# RAK3112_RS485_P2P_Node_V1_1.net
KiCad netlist of a schematic drawn in EasyEDA Pro
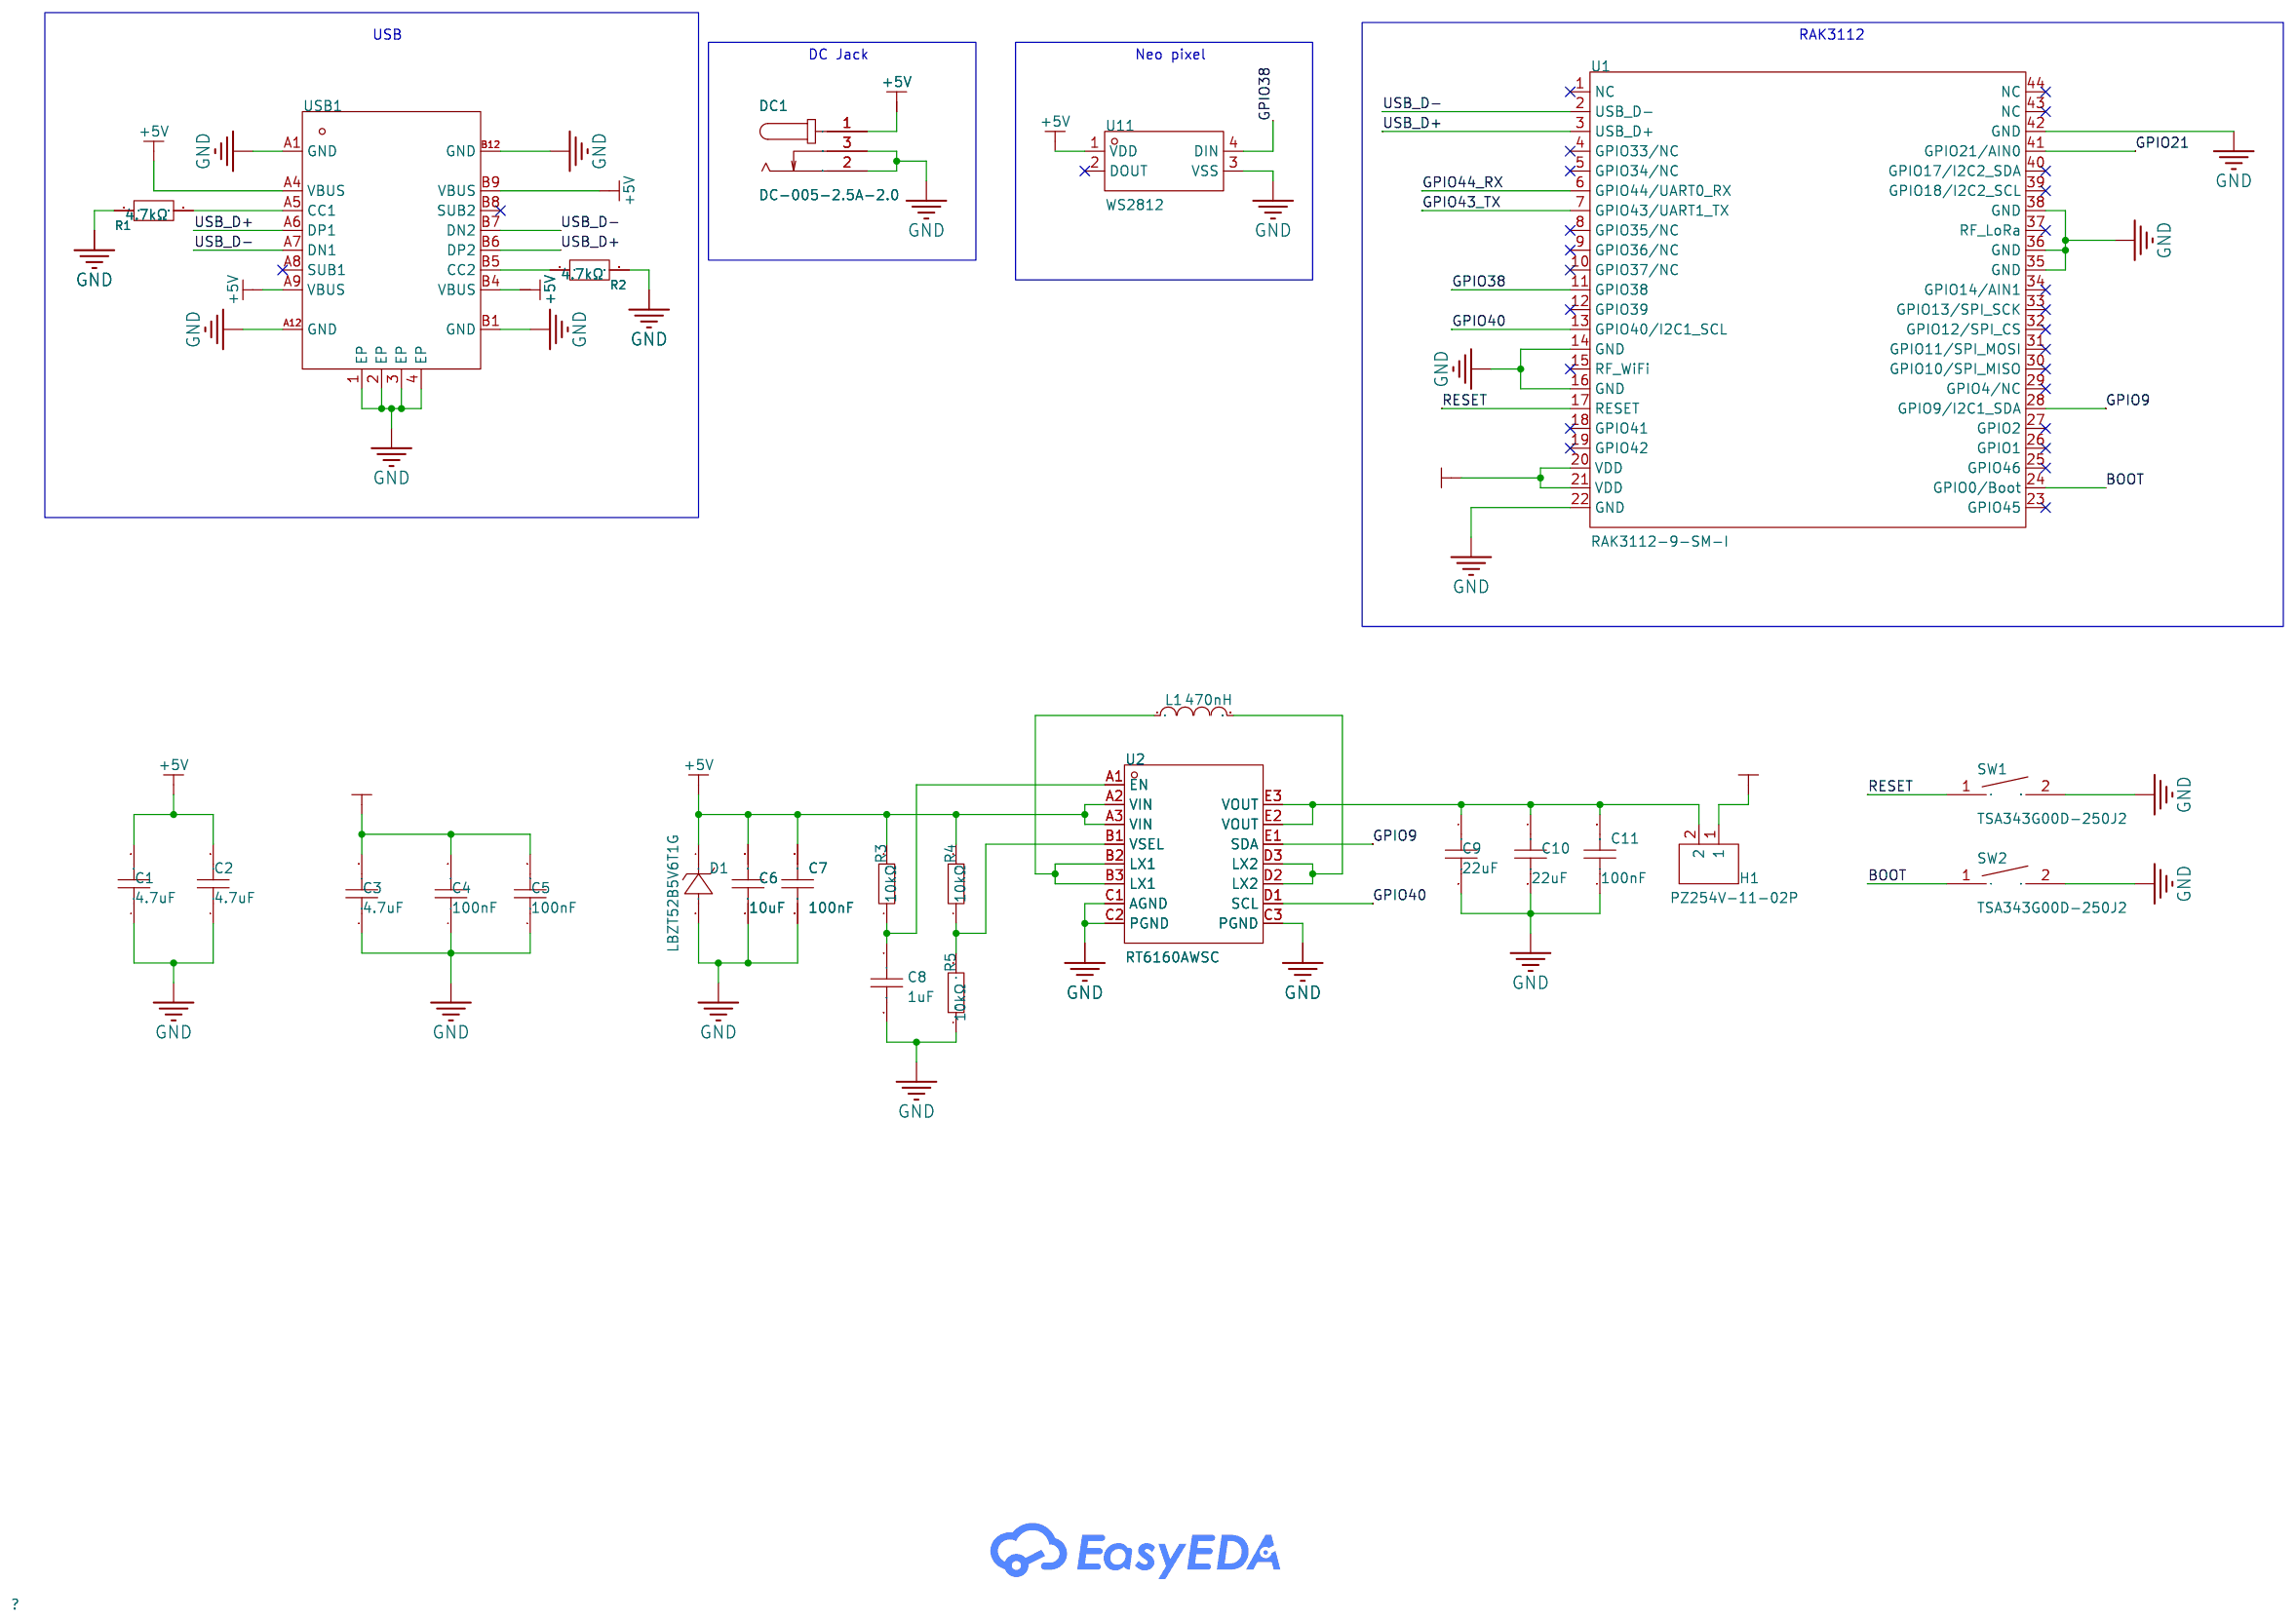
[diagram p0: P1]
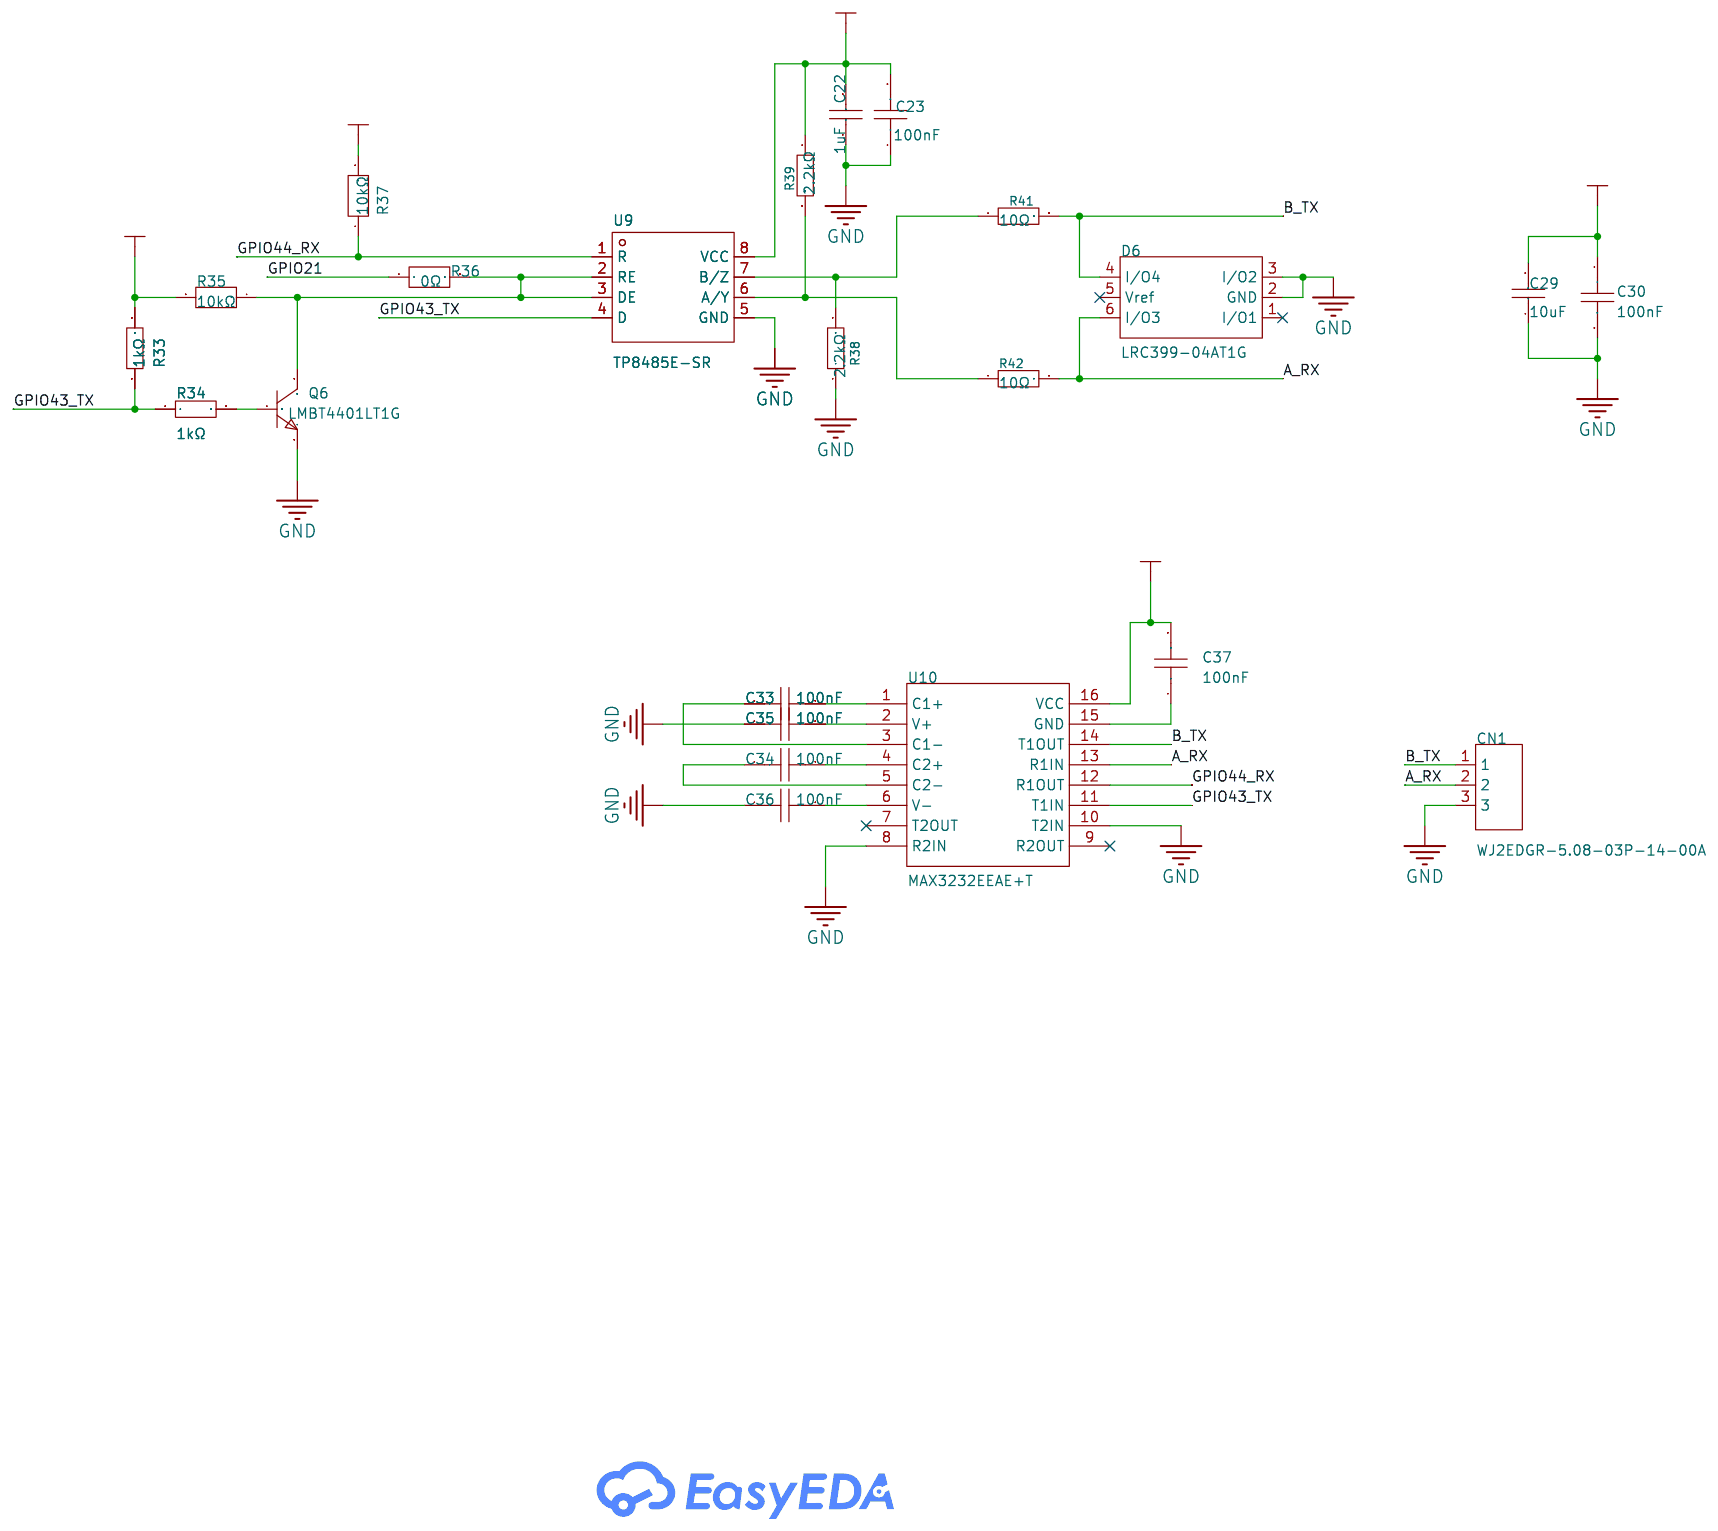
[diagram p1: RS484]

(export (version "E")
  (design (tool "Eeschema 10.0.6"))
  (components
    (comp (ref "C1")
      (value "4.7uF")
      (footprint "easyedapro:C0603")
      (description "Capacitance:4.7uF Tolerance:±10% Tolerance:±10% Voltage Rating:16V Temperature Coefficient:X5R")
      (fields
        (field (name "Manufacturer Part") "CL10A475KO8NNNC")
        (field (name "Manufacturer") "SAMSUNG(三星)")
      )
      (libsource (lib "easyedapro") (part "CL10A475KO8NNNC"))
    )
    (comp (ref "C2")
      (value "4.7uF")
      (footprint "easyedapro:C0603")
      (description "Capacitance:4.7uF Tolerance:±10% Tolerance:±10% Voltage Rating:16V Temperature Coefficient:X5R")
      (fields
        (field (name "Manufacturer Part") "CL10A475KO8NNNC")
        (field (name "Manufacturer") "SAMSUNG(三星)")
      )
      (libsource (lib "easyedapro") (part "CL10A475KO8NNNC"))
    )
    (comp (ref "C3")
      (value "4.7uF")
      (footprint "easyedapro:C0603")
      (description "Capacitance:4.7uF Tolerance:±10% Tolerance:±10% Voltage Rating:16V Temperature Coefficient:X5R")
      (fields
        (field (name "Manufacturer Part") "CL10A475KO8NNNC")
        (field (name "Manufacturer") "SAMSUNG(三星)")
      )
      (libsource (lib "easyedapro") (part "CL10A475KO8NNNC"))
    )
    (comp (ref "C4")
      (value "100nF")
      (footprint "easyedapro:C0603")
      (description "Capacitance:100nF Tolerance:±10% Tolerance:±10% Voltage Rating:50V Temperature Coefficient:X7R")
      (fields
        (field (name "Manufacturer Part") "TCC0603X7R104K500CT")
        (field (name "Manufacturer") "CCTC(三环)")
      )
      (libsource (lib "easyedapro") (part "TCC0603X7R104K500CT"))
    )
    (comp (ref "C5")
      (value "100nF")
      (footprint "easyedapro:C0603")
      (description "Capacitance:100nF Tolerance:±10% Tolerance:±10% Voltage Rating:50V Temperature Coefficient:X7R")
      (fields
        (field (name "Manufacturer Part") "TCC0603X7R104K500CT")
        (field (name "Manufacturer") "CCTC(三环)")
      )
      (libsource (lib "easyedapro") (part "TCC0603X7R104K500CT"))
    )
    (comp (ref "C6")
      (value "10uF")
      (footprint "easyedapro:C0603")
      (description "Capacitance:10uF Tolerance:±10% Tolerance:±10% Voltage Rating:10V Temperature Coefficient:X5R")
      (fields
        (field (name "Manufacturer Part") "CGA0603X5R106K100JT")
        (field (name "Manufacturer") "HRE(芯声)")
      )
      (libsource (lib "easyedapro") (part "CGA0603X5R106K100JT"))
    )
    (comp (ref "C7")
      (value "100nF")
      (footprint "easyedapro:C0603")
      (description "Capacitance:100nF Tolerance:±10% Tolerance:±10% Voltage Rating:50V Temperature Coefficient:X7R")
      (fields
        (field (name "Manufacturer Part") "TCC0603X7R104K500CT")
        (field (name "Manufacturer") "CCTC(三环)")
      )
      (libsource (lib "easyedapro") (part "TCC0603X7R104K500CT"))
    )
    (comp (ref "C8")
      (value "1uF")
      (footprint "easyedapro:C0603")
      (description "Capacitance:1uF Tolerance:±10% Tolerance:±10% Voltage Rating:50V Temperature Coefficient:X7R")
      (fields
        (field (name "Manufacturer Part") "CL10B105KB8NQNC")
        (field (name "Manufacturer") "SAMSUNG(三星)")
      )
      (libsource (lib "easyedapro") (part "CL10B105KB8NQNC"))
    )
    (comp (ref "C9")
      (value "22uF")
      (footprint "easyedapro:C0603")
      (description "Capacitance:22uF Tolerance:±20% Tolerance:±20% Voltage Rating:6.3V Temperature Coefficient:X5R")
      (fields
        (field (name "Manufacturer Part") "CL10A226MQ8NRNC")
        (field (name "Manufacturer") "SAMSUNG(三星)")
      )
      (libsource (lib "easyedapro") (part "CL10A226MQ8NRNC"))
    )
    (comp (ref "C10")
      (value "22uF")
      (footprint "easyedapro:C0603")
      (description "Capacitance:22uF Tolerance:±20% Tolerance:±20% Voltage Rating:6.3V Temperature Coefficient:X5R")
      (fields
        (field (name "Manufacturer Part") "CL10A226MQ8NRNC")
        (field (name "Manufacturer") "SAMSUNG(三星)")
      )
      (libsource (lib "easyedapro") (part "CL10A226MQ8NRNC"))
    )
    (comp (ref "C11")
      (value "100nF")
      (footprint "easyedapro:C0603")
      (description "Capacitance:100nF Tolerance:±10% Tolerance:±10% Voltage Rating:50V Temperature Coefficient:X7R")
      (fields
        (field (name "Manufacturer Part") "TCC0603X7R104K500CT")
        (field (name "Manufacturer") "CCTC(三环)")
      )
      (libsource (lib "easyedapro") (part "TCC0603X7R104K500CT"))
    )
    (comp (ref "D1")
      (value "LBZT52B5V6T1G")
      (footprint "easyedapro:SOD-123_L2.7-W1.6-LS3.7-RD-1")
      (fields (field (name "Manufacturer") "LRC(乐山无线电)"))
      (libsource (lib "easyedapro") (part "LBZT52B5V6T1G"))
    )
    (comp (ref "DC1")
      (value "DC-005-2.5A-2.0")
      (footprint "easyedapro:CONN-TH_DC-005-2.5A-2.0")
      (fields (field (name "Manufacturer") "XKB Connection(中国星坤)"))
      (libsource (lib "easyedapro") (part "DC-005-2.5A-2.0"))
    )
    (comp (ref "H1")
      (value "PZ254V-11-02P")
      (footprint "easyedapro:HDR-TH_2P-P2.54-V-M")
      (fields (field (name "Manufacturer") "XFCN(兴飞)"))
      (libsource (lib "easyedapro") (part "PZ254V-11-02P"))
    )
    (comp (ref "L1")
      (value "470nH")
      (footprint "easyedapro:IND-SMD_L4.4-W4.2")
      (fields (field (name "Manufacturer Part") "FXL0420-R47-M") (field (name "Manufacturer") "cjiang(长江微电)"))
      (libsource (lib "easyedapro") (part "FXL0420-R47-M"))
    )
    (comp (ref "R1")
      (value "4.7kΩ")
      (footprint "easyedapro:R0603")
      (fields (field (name "Manufacturer Part") "FRC0603J472 TS") (field (name "Manufacturer") "FOJAN(富捷)"))
      (libsource (lib "easyedapro") (part "FRC0603J472 TS"))
    )
    (comp (ref "R2")
      (value "4.7kΩ")
      (footprint "easyedapro:R0603")
      (fields (field (name "Manufacturer Part") "FRC0603J472 TS") (field (name "Manufacturer") "FOJAN(富捷)"))
      (libsource (lib "easyedapro") (part "FRC0603J472 TS"))
    )
    (comp (ref "R3")
      (value "10kΩ")
      (footprint "easyedapro:R0603")
      (fields (field (name "Manufacturer Part") "RC0603FR-0710KL") (field (name "Manufacturer") "YAGEO(国巨)"))
      (libsource (lib "easyedapro") (part "RC0603FR-0710KL"))
    )
    (comp (ref "R4")
      (value "10kΩ")
      (footprint "easyedapro:R0603")
      (fields (field (name "Manufacturer Part") "RC0603FR-0710KL") (field (name "Manufacturer") "YAGEO(国巨)"))
      (libsource (lib "easyedapro") (part "RC0603FR-0710KL"))
    )
    (comp (ref "R5")
      (value "10kΩ")
      (footprint "easyedapro:R0603")
      (fields (field (name "Manufacturer Part") "RC0603FR-0710KL") (field (name "Manufacturer") "YAGEO(国巨)"))
      (libsource (lib "easyedapro") (part "RC0603FR-0710KL"))
    )
    (comp (ref "SW1")
      (value "TSA343G00D-250J2")
      (footprint "easyedapro:SW-SMD_L4.0-W2.9-P4.15-EH")
      (fields (field (name "Manufacturer") "BRIGHT(博瑞泰)"))
      (libsource (lib "easyedapro") (part "TSA343G00D-250J2"))
    )
    (comp (ref "SW2")
      (value "TSA343G00D-250J2")
      (footprint "easyedapro:SW-SMD_L4.0-W2.9-P4.15-EH")
      (fields (field (name "Manufacturer") "BRIGHT(博瑞泰)"))
      (libsource (lib "easyedapro") (part "TSA343G00D-250J2"))
    )
    (comp (ref "U1")
      (value "RAK3112-9-SM-I")
      (footprint "easyedapro:COMM-SMD_44P-L23.0-W15.0-P1.20_RAK3112-9-SM-I")
      (fields (field (name "Manufacturer") "RAK(瑞科慧联)"))
      (libsource (lib "easyedapro") (part "RAK3112-9-SM-I"))
    )
    (comp (ref "U2")
      (value "RT6160AWSC")
      (footprint "easyedapro:WLCSP-15_L2.3-W1.4-R3-C5-P0.40-BL")
      (fields (field (name "Manufacturer") "RICHTEK(立锜)"))
      (libsource (lib "easyedapro") (part "RT6160AWSC"))
    )
    (comp (ref "U11")
      (value "WS2812")
      (footprint "easyedapro:LED-SMD_4P-L5.0-W5.0-TL-A")
      (fields (field (name "Manufacturer") "worldsemi"))
      (libsource (lib "easyedapro") (part "WS2812"))
    )
    (comp (ref "USB1")
      (value "~")
      (footprint "easyedapro:USB-C-SMD_KH-TYPE-C-16P")
      (libsource (lib "easyedapro") (part "KH-TYPE-C-16P"))
    )
    (comp (ref "C22")
      (value "1uF")
      (footprint "easyedapro:C0402")
      (description "Capacitance:1uF Tolerance:±10% Tolerance:±10% Voltage Rating:10V Temperature Coefficient:X5R")
      (fields
        (field (name "Manufacturer Part") "CL05A105KP5NNNC")
        (field (name "Manufacturer") "SAMSUNG(三星)")
      )
      (libsource (lib "easyedapro") (part "CL05A105KP5NNNC"))
    )
    (comp (ref "C23")
      (value "100nF")
      (footprint "easyedapro:C0402")
      (description "Capacitance:100nF Tolerance:±10% Tolerance:±10% Voltage Rating:16V Temperature Coefficient:X7R")
      (fields
        (field (name "Manufacturer Part") "FCC0402B104K160AT")
        (field (name "Manufacturer") "FOJAN(富捷)")
      )
      (libsource (lib "easyedapro") (part "FCC0402B104K160AT"))
    )
    (comp (ref "C29")
      (value "10uF")
      (footprint "easyedapro:C0402")
      (description "Capacitance:10uF Tolerance:±20% Tolerance:±20% Voltage Rating:6.3V Temperature Coefficient:X5R")
      (fields
        (field (name "Manufacturer Part") "GRM155R60J106ME44D")
        (field (name "Manufacturer") "muRata(村田)")
      )
      (libsource (lib "easyedapro") (part "GRM155R60J106ME44D"))
    )
    (comp (ref "C30")
      (value "100nF")
      (footprint "easyedapro:C0402")
      (description "Capacitance:100nF Tolerance:±10% Tolerance:±10% Voltage Rating:16V Temperature Coefficient:X7R")
      (fields
        (field (name "Manufacturer Part") "FCC0402B104K160AT")
        (field (name "Manufacturer") "FOJAN(富捷)")
      )
      (libsource (lib "easyedapro") (part "FCC0402B104K160AT"))
    )
    (comp (ref "C33")
      (value "100nF")
      (footprint "easyedapro:C0603")
      (fields
        (field (name "Manufacturer Part") "CGA0603X7R104K100JT")
        (field (name "Manufacturer") "HRE(芯声)")
      )
      (libsource (lib "easyedapro") (part "CGA0603X7R104K100JT"))
    )
    (comp (ref "C34")
      (value "100nF")
      (footprint "easyedapro:C0603")
      (fields
        (field (name "Manufacturer Part") "CGA0603X7R104K100JT")
        (field (name "Manufacturer") "HRE(芯声)")
      )
      (libsource (lib "easyedapro") (part "CGA0603X7R104K100JT"))
    )
    (comp (ref "C35")
      (value "100nF")
      (footprint "easyedapro:C0603")
      (fields
        (field (name "Manufacturer Part") "CGA0603X7R104K100JT")
        (field (name "Manufacturer") "HRE(芯声)")
      )
      (libsource (lib "easyedapro") (part "CGA0603X7R104K100JT"))
    )
    (comp (ref "C36")
      (value "100nF")
      (footprint "easyedapro:C0603")
      (fields
        (field (name "Manufacturer Part") "CGA0603X7R104K100JT")
        (field (name "Manufacturer") "HRE(芯声)")
      )
      (libsource (lib "easyedapro") (part "CGA0603X7R104K100JT"))
    )
    (comp (ref "C37")
      (value "100nF")
      (footprint "easyedapro:C0603")
      (fields
        (field (name "Manufacturer Part") "CGA0603X7R104K100JT")
        (field (name "Manufacturer") "HRE(芯声)")
      )
      (libsource (lib "easyedapro") (part "CGA0603X7R104K100JT"))
    )
    (comp (ref "CN1")
      (value "WJ2EDGR-5.08-03P-14-00A")
      (footprint "easyedapro:CONN-TH_3P-P5.08_WJ2EDGR-5.08-3P")
      (fields (field (name "Manufacturer") "KANGNEX(康奈克斯电气)"))
      (libsource (lib "easyedapro") (part "WJ2EDGR-5.08-3P"))
    )
    (comp (ref "D6")
      (value "LRC399-04AT1G")
      (footprint "easyedapro:TSOP-6_L3.0-W1.5-P0.95-BL")
      (fields (field (name "Manufacturer") "LRC(乐山无线电)"))
      (libsource (lib "easyedapro") (part "LRC399-04AT1G"))
    )
    (comp (ref "Q6")
      (value "LMBT4401LT1G")
      (footprint "easyedapro:SOT-23-3_L2.9-W1.3-P1.90-LS2.4-BR")
      (fields (field (name "Manufacturer") "LRC(乐山无线电)"))
      (libsource (lib "easyedapro") (part "LMBT4401LT1G"))
    )
    (comp (ref "R33")
      (value "1kΩ")
      (footprint "easyedapro:R0402")
      (fields
        (field (name "Manufacturer Part") "0402WGF1001TCE")
        (field (name "Manufacturer") "UNI-ROYAL(厚声)")
      )
      (libsource (lib "easyedapro") (part "0402WGF1001TCE"))
    )
    (comp (ref "R34")
      (value "1kΩ")
      (footprint "easyedapro:R0402")
      (fields
        (field (name "Manufacturer Part") "0402WGF1001TCE")
        (field (name "Manufacturer") "UNI-ROYAL(厚声)")
      )
      (libsource (lib "easyedapro") (part "0402WGF1001TCE"))
    )
    (comp (ref "R35")
      (value "10kΩ")
      (footprint "easyedapro:R0603")
      (fields (field (name "Manufacturer Part") "FRC0603J103 TS") (field (name "Manufacturer") "FOJAN(富捷)"))
      (libsource (lib "easyedapro") (part "FRC0603J103TS"))
    )
    (comp (ref "R36")
      (value "0Ω")
      (footprint "easyedapro:R0805")
      (description "Resistance:0Ω Power(Watts):500mW")
      (fields (field (name "Manufacturer Part") "YLRY05-W2-0Z") (field (name "Manufacturer") "yezhan(业展)"))
      (libsource (lib "easyedapro") (part "YLRY05-W2-0Z"))
    )
    (comp (ref "R37")
      (value "10kΩ")
      (footprint "easyedapro:R0603")
      (fields (field (name "Manufacturer Part") "FRC0603J103 TS") (field (name "Manufacturer") "FOJAN(富捷)"))
      (libsource (lib "easyedapro") (part "FRC0603J103TS"))
    )
    (comp (ref "R38")
      (value "2.2kΩ")
      (footprint "easyedapro:R0402")
      (fields
        (field (name "Manufacturer Part") "0402WGF2201TCE")
        (field (name "Manufacturer") "UNI-ROYAL(厚声)")
      )
      (libsource (lib "easyedapro") (part "0402WGF2201TCE"))
    )
    (comp (ref "R39")
      (value "2.2kΩ")
      (footprint "easyedapro:R0402")
      (fields
        (field (name "Manufacturer Part") "0402WGF2201TCE")
        (field (name "Manufacturer") "UNI-ROYAL(厚声)")
      )
      (libsource (lib "easyedapro") (part "0402WGF2201TCE"))
    )
    (comp (ref "R41")
      (value "10Ω")
      (footprint "easyedapro:R0402")
      (fields
        (field (name "Manufacturer Part") "0402WGF100JTCE")
        (field (name "Manufacturer") "UNI-ROYAL(厚声)")
      )
      (libsource (lib "easyedapro") (part "0402WGF100JTCE"))
    )
    (comp (ref "R42")
      (value "10Ω")
      (footprint "easyedapro:R0402")
      (fields
        (field (name "Manufacturer Part") "0402WGF100JTCE")
        (field (name "Manufacturer") "UNI-ROYAL(厚声)")
      )
      (libsource (lib "easyedapro") (part "0402WGF100JTCE"))
    )
    (comp (ref "U9")
      (value "TP8485E-SR")
      (footprint "easyedapro:SOIC-8_L5.0-W4.0-P1.27-LS6.0-BL")
      (fields (field (name "Manufacturer") "3PEAK(思瑞浦)"))
      (libsource (lib "easyedapro") (part "TP8485E-SR"))
    )
    (comp (ref "U10")
      (value "MAX3232EEAE+T")
      (footprint "easyedapro:SSOP-16_L6.2-W5.3-P0.65-LS7.8-BL")
      (fields (field (name "Manufacturer") "ADI(亚德诺)/MAXIM(美信)"))
      (libsource (lib "easyedapro") (part "MAX3232EEAE+"))
    )
  )
  (nets
    (net (code "1") (name "+5V") (class "Default")
      (node (ref "C1") (pin "2") (pinfunction "2_2") (pintype "unspecified"))
      (node (ref "C2") (pin "2") (pinfunction "2_2") (pintype "unspecified"))
      (node (ref "C6") (pin "2") (pinfunction "2_2") (pintype "unspecified"))
      (node (ref "C7") (pin "2") (pinfunction "2_2") (pintype "unspecified"))
      (node (ref "D1") (pin "1") (pinfunction "K_1") (pintype "unspecified"))
      (node (ref "DC1") (pin "1") (pinfunction "1_1") (pintype "unspecified"))
      (node (ref "R3") (pin "2") (pinfunction "2_2") (pintype "input"))
      (node (ref "R4") (pin "2") (pinfunction "2_2") (pintype "input"))
      (node (ref "U11") (pin "1") (pinfunction "VDD_1") (pintype "unspecified"))
      (node (ref "U2") (pin "A2") (pinfunction "VIN_A2") (pintype "unspecified"))
      (node (ref "U2") (pin "A3") (pinfunction "VIN_A3") (pintype "unspecified"))
      (node (ref "USB1") (pin "A4") (pinfunction "VBUS_A4") (pintype "unspecified"))
      (node (ref "USB1") (pin "A9") (pinfunction "VBUS_A9") (pintype "unspecified"))
      (node (ref "USB1") (pin "B4") (pinfunction "VBUS_B4") (pintype "unspecified"))
      (node (ref "USB1") (pin "B9") (pinfunction "VBUS_B9") (pintype "unspecified"))
    )
    (net (code "2") (name "3V3") (class "Default")
      (node (ref "C22") (pin "2") (pinfunction "2_2") (pintype "input"))
      (node (ref "C23") (pin "2") (pinfunction "2_2") (pintype "unspecified"))
      (node (ref "C29") (pin "2") (pinfunction "2_2") (pintype "input"))
      (node (ref "C3") (pin "2") (pinfunction "2_2") (pintype "unspecified"))
      (node (ref "C30") (pin "1") (pinfunction "1_1") (pintype "unspecified"))
      (node (ref "C37") (pin "2") (pinfunction "2_2") (pintype "unspecified"))
      (node (ref "C4") (pin "2") (pinfunction "2_2") (pintype "unspecified"))
      (node (ref "C5") (pin "2") (pinfunction "2_2") (pintype "unspecified"))
      (node (ref "H1") (pin "1") (pinfunction "1_1") (pintype "unspecified"))
      (node (ref "R33") (pin "2") (pinfunction "2_2") (pintype "input"))
      (node (ref "R35") (pin "2") (pinfunction "2_2") (pintype "unspecified"))
      (node (ref "R37") (pin "2") (pinfunction "2_2") (pintype "unspecified"))
      (node (ref "R39") (pin "1") (pinfunction "1_1") (pintype "input"))
      (node (ref "U1") (pin "20") (pinfunction "VDD_20") (pintype "unspecified"))
      (node (ref "U1") (pin "21") (pinfunction "VDD_21") (pintype "unspecified"))
      (node (ref "U10") (pin "16") (pinfunction "VCC_16") (pintype "unspecified"))
      (node (ref "U9") (pin "8") (pinfunction "VCC_8") (pintype "unspecified"))
    )
    (net (code "3") (name "A_RX") (class "Default")
      (node (ref "CN1") (pin "2") (pinfunction "2_2") (pintype "unspecified"))
      (node (ref "D6") (pin "6") (pinfunction "I/O3_6") (pintype "unspecified"))
      (node (ref "R42") (pin "2") (pinfunction "2_2") (pintype "input"))
      (node (ref "U10") (pin "13") (pinfunction "R1IN_13") (pintype "unspecified"))
    )
    (net (code "4") (name "BOOT") (class "Default")
      (node (ref "SW2") (pin "1") (pinfunction "1_1") (pintype "input"))
      (node (ref "U1") (pin "24") (pinfunction "GPIO0/Boot_24") (pintype "unspecified"))
    )
    (net (code "5") (name "B_TX") (class "Default")
      (node (ref "CN1") (pin "1") (pinfunction "1_1") (pintype "unspecified"))
      (node (ref "D6") (pin "4") (pinfunction "I/O4_4") (pintype "unspecified"))
      (node (ref "R41") (pin "2") (pinfunction "2_2") (pintype "input"))
      (node (ref "U10") (pin "14") (pinfunction "T1OUT_14") (pintype "unspecified"))
    )
    (net (code "6") (name "GND") (class "Default")
      (node (ref "C1") (pin "1") (pinfunction "1_1") (pintype "unspecified"))
      (node (ref "C10") (pin "2") (pinfunction "2_2") (pintype "unspecified"))
      (node (ref "C11") (pin "1") (pinfunction "1_1") (pintype "unspecified"))
      (node (ref "C2") (pin "1") (pinfunction "1_1") (pintype "unspecified"))
      (node (ref "C22") (pin "1") (pinfunction "1_1") (pintype "input"))
      (node (ref "C23") (pin "1") (pinfunction "1_1") (pintype "unspecified"))
      (node (ref "C29") (pin "1") (pinfunction "1_1") (pintype "input"))
      (node (ref "C3") (pin "1") (pinfunction "1_1") (pintype "unspecified"))
      (node (ref "C30") (pin "2") (pinfunction "2_2") (pintype "unspecified"))
      (node (ref "C35") (pin "1") (pinfunction "1_1") (pintype "unspecified"))
      (node (ref "C36") (pin "1") (pinfunction "1_1") (pintype "unspecified"))
      (node (ref "C4") (pin "1") (pinfunction "1_1") (pintype "unspecified"))
      (node (ref "C5") (pin "1") (pinfunction "1_1") (pintype "unspecified"))
      (node (ref "C6") (pin "1") (pinfunction "1_1") (pintype "unspecified"))
      (node (ref "C7") (pin "1") (pinfunction "1_1") (pintype "unspecified"))
      (node (ref "C8") (pin "2") (pinfunction "2_2") (pintype "unspecified"))
      (node (ref "C9") (pin "2") (pinfunction "2_2") (pintype "unspecified"))
      (node (ref "CN1") (pin "3") (pinfunction "3_3") (pintype "unspecified"))
      (node (ref "D1") (pin "2") (pinfunction "A_2") (pintype "unspecified"))
      (node (ref "D6") (pin "2") (pinfunction "GND_2") (pintype "unspecified"))
      (node (ref "D6") (pin "3") (pinfunction "I/O2_3") (pintype "unspecified"))
      (node (ref "DC1") (pin "2") (pinfunction "2_2") (pintype "unspecified"))
      (node (ref "DC1") (pin "3") (pinfunction "3_3") (pintype "unspecified"))
      (node (ref "Q6") (pin "2") (pinfunction "E_2") (pintype "unspecified"))
      (node (ref "R1") (pin "1") (pinfunction "1_1") (pintype "input"))
      (node (ref "R2") (pin "2") (pinfunction "2_2") (pintype "input"))
      (node (ref "R38") (pin "1") (pinfunction "1_1") (pintype "input"))
      (node (ref "R5") (pin "1") (pinfunction "1_1") (pintype "input"))
      (node (ref "SW1") (pin "2") (pinfunction "2_2") (pintype "input"))
      (node (ref "SW2") (pin "2") (pinfunction "2_2") (pintype "input"))
      (node (ref "U1") (pin "14") (pinfunction "GND_14") (pintype "unspecified"))
      (node (ref "U1") (pin "16") (pinfunction "GND_16") (pintype "unspecified"))
      (node (ref "U1") (pin "22") (pinfunction "GND_22") (pintype "unspecified"))
      (node (ref "U1") (pin "35") (pinfunction "GND_35") (pintype "unspecified"))
      (node (ref "U1") (pin "36") (pinfunction "GND_36") (pintype "unspecified"))
      (node (ref "U1") (pin "38") (pinfunction "GND_38") (pintype "unspecified"))
      (node (ref "U1") (pin "42") (pinfunction "GND_42") (pintype "unspecified"))
      (node (ref "U10") (pin "10") (pinfunction "T2IN_10") (pintype "unspecified"))
      (node (ref "U10") (pin "8") (pinfunction "R2IN_8") (pintype "unspecified"))
      (node (ref "U11") (pin "3") (pinfunction "VSS_3") (pintype "unspecified"))
      (node (ref "U2") (pin "C1") (pinfunction "AGND_C1") (pintype "unspecified"))
      (node (ref "U2") (pin "C2") (pinfunction "PGND_C2") (pintype "unspecified"))
      (node (ref "U2") (pin "C3") (pinfunction "PGND_C3") (pintype "unspecified"))
      (node (ref "U9") (pin "5") (pinfunction "GND_5") (pintype "unspecified"))
      (node (ref "USB1") (pin "1") (pinfunction "EP_1") (pintype "unspecified"))
      (node (ref "USB1") (pin "2") (pinfunction "EP_2") (pintype "unspecified"))
      (node (ref "USB1") (pin "3") (pinfunction "EP_3") (pintype "unspecified"))
      (node (ref "USB1") (pin "4") (pinfunction "EP_4") (pintype "unspecified"))
      (node (ref "USB1") (pin "A1") (pinfunction "GND_A1") (pintype "unspecified"))
      (node (ref "USB1") (pin "A12") (pinfunction "GND_A12") (pintype "unspecified"))
      (node (ref "USB1") (pin "B1") (pinfunction "GND_B1") (pintype "unspecified"))
      (node (ref "USB1") (pin "B12") (pinfunction "GND_B12") (pintype "unspecified"))
    )
    (net (code "7") (name "GPIO9") (class "Default")
      (node (ref "U1") (pin "28") (pinfunction "GPIO9/I2C1_SDA_28") (pintype "unspecified"))
      (node (ref "U2") (pin "E1") (pinfunction "SDA_E1") (pintype "unspecified"))
    )
    (net (code "8") (name "GPIO21") (class "Default")
      (node (ref "R36") (pin "1") (pinfunction "1_1") (pintype "unspecified"))
      (node (ref "U1") (pin "41") (pinfunction "GPIO21/AIN0_41") (pintype "unspecified"))
    )
    (net (code "9") (name "GPIO38") (class "Default")
      (node (ref "U1") (pin "11") (pinfunction "GPIO38_11") (pintype "unspecified"))
      (node (ref "U11") (pin "4") (pinfunction "DIN_4") (pintype "unspecified"))
    )
    (net (code "10") (name "GPIO40") (class "Default")
      (node (ref "U1") (pin "13") (pinfunction "GPIO40/I2C1_SCL_13") (pintype "unspecified"))
      (node (ref "U2") (pin "D1") (pinfunction "SCL_D1") (pintype "unspecified"))
    )
    (net (code "11") (name "GPIO43_TX") (class "Default")
      (node (ref "R33") (pin "1") (pinfunction "1_1") (pintype "input"))
      (node (ref "R34") (pin "1") (pinfunction "1_1") (pintype "input"))
      (node (ref "U1") (pin "7") (pinfunction "GPIO43/UART1_TX_7") (pintype "unspecified"))
      (node (ref "U10") (pin "11") (pinfunction "T1IN_11") (pintype "unspecified"))
      (node (ref "U9") (pin "4") (pinfunction "D_4") (pintype "unspecified"))
    )
    (net (code "12") (name "GPIO44_RX") (class "Default")
      (node (ref "R37") (pin "1") (pinfunction "1_1") (pintype "unspecified"))
      (node (ref "U1") (pin "6") (pinfunction "GPIO44/UART0_RX_6") (pintype "unspecified"))
      (node (ref "U10") (pin "12") (pinfunction "R1OUT_12") (pintype "unspecified"))
      (node (ref "U9") (pin "1") (pinfunction "R_1") (pintype "unspecified"))
    )
    (net (code "13") (name "Net-(C10-Pad1)") (class "Default")
      (node (ref "C10") (pin "1") (pinfunction "1_1") (pintype "unspecified"))
      (node (ref "C11") (pin "2") (pinfunction "2_2") (pintype "unspecified"))
      (node (ref "C9") (pin "1") (pinfunction "1_1") (pintype "unspecified"))
      (node (ref "H1") (pin "2") (pinfunction "2_2") (pintype "unspecified"))
      (node (ref "U2") (pin "E2") (pinfunction "VOUT_E2") (pintype "unspecified"))
      (node (ref "U2") (pin "E3") (pinfunction "VOUT_E3") (pintype "unspecified"))
    )
    (net (code "14") (name "Net-(L1-Pad1)") (class "Default")
      (node (ref "L1") (pin "1") (pinfunction "1_1") (pintype "unspecified"))
      (node (ref "U2") (pin "B2") (pinfunction "LX1_B2") (pintype "unspecified"))
      (node (ref "U2") (pin "B3") (pinfunction "LX1_B3") (pintype "unspecified"))
    )
    (net (code "15") (name "Net-(L1-Pad2)") (class "Default")
      (node (ref "L1") (pin "2") (pinfunction "2_2") (pintype "unspecified"))
      (node (ref "U2") (pin "D2") (pinfunction "LX2_D2") (pintype "unspecified"))
      (node (ref "U2") (pin "D3") (pinfunction "LX2_D3") (pintype "unspecified"))
    )
    (net (code "16") (name "Net-(Q6-B)") (class "Default")
      (node (ref "Q6") (pin "1") (pinfunction "B_1") (pintype "unspecified"))
      (node (ref "R34") (pin "2") (pinfunction "2_2") (pintype "input"))
    )
    (net (code "17") (name "Net-(Q6-C)") (class "Default")
      (node (ref "Q6") (pin "3") (pinfunction "C_3") (pintype "unspecified"))
      (node (ref "R35") (pin "1") (pinfunction "1_1") (pintype "unspecified"))
      (node (ref "R36") (pin "2") (pinfunction "2_2") (pintype "unspecified"))
      (node (ref "U9") (pin "2") (pinfunction "RE_2") (pintype "unspecified"))
      (node (ref "U9") (pin "3") (pinfunction "DE_3") (pintype "unspecified"))
    )
    (net (code "18") (name "Net-(U2-EN)") (class "Default")
      (node (ref "C8") (pin "1") (pinfunction "1_1") (pintype "unspecified"))
      (node (ref "R3") (pin "1") (pinfunction "1_1") (pintype "input"))
      (node (ref "U2") (pin "A1") (pinfunction "EN_A1") (pintype "unspecified"))
    )
    (net (code "19") (name "Net-(U2-VSEL)") (class "Default")
      (node (ref "R4") (pin "1") (pinfunction "1_1") (pintype "input"))
      (node (ref "R5") (pin "2") (pinfunction "2_2") (pintype "input"))
      (node (ref "U2") (pin "B1") (pinfunction "VSEL_B1") (pintype "unspecified"))
    )
    (net (code "20") (name "Net-(U9-A{slash}Y)") (class "Default")
      (node (ref "R39") (pin "2") (pinfunction "2_2") (pintype "input"))
      (node (ref "R42") (pin "1") (pinfunction "1_1") (pintype "input"))
      (node (ref "U9") (pin "6") (pinfunction "A/Y_6") (pintype "unspecified"))
    )
    (net (code "21") (name "Net-(U9-B{slash}Z)") (class "Default")
      (node (ref "R38") (pin "2") (pinfunction "2_2") (pintype "input"))
      (node (ref "R41") (pin "1") (pinfunction "1_1") (pintype "input"))
      (node (ref "U9") (pin "7") (pinfunction "B/Z_7") (pintype "unspecified"))
    )
    (net (code "22") (name "Net-(U10-C1+)") (class "Default")
      (node (ref "C33") (pin "2") (pinfunction "2_2") (pintype "unspecified"))
      (node (ref "U10") (pin "1") (pinfunction "C1+_1") (pintype "unspecified"))
    )
    (net (code "23") (name "Net-(U10-C1-)") (class "Default")
      (node (ref "C33") (pin "1") (pinfunction "1_1") (pintype "unspecified"))
      (node (ref "U10") (pin "3") (pinfunction "C1-_3") (pintype "unspecified"))
    )
    (net (code "24") (name "Net-(U10-C2+)") (class "Default")
      (node (ref "C34") (pin "2") (pinfunction "2_2") (pintype "unspecified"))
      (node (ref "U10") (pin "4") (pinfunction "C2+_4") (pintype "unspecified"))
    )
    (net (code "25") (name "Net-(U10-C2-)") (class "Default")
      (node (ref "C34") (pin "1") (pinfunction "1_1") (pintype "unspecified"))
      (node (ref "U10") (pin "5") (pinfunction "C2-_5") (pintype "unspecified"))
    )
    (net (code "26") (name "Net-(U10-GND)") (class "Default")
      (node (ref "C37") (pin "1") (pinfunction "1_1") (pintype "unspecified"))
      (node (ref "U10") (pin "15") (pinfunction "GND_15") (pintype "unspecified"))
    )
    (net (code "27") (name "Net-(U10-V+)") (class "Default")
      (node (ref "C35") (pin "2") (pinfunction "2_2") (pintype "unspecified"))
      (node (ref "U10") (pin "2") (pinfunction "V+_2") (pintype "unspecified"))
    )
    (net (code "28") (name "Net-(U10-V-)") (class "Default")
      (node (ref "C36") (pin "2") (pinfunction "2_2") (pintype "unspecified"))
      (node (ref "U10") (pin "6") (pinfunction "V-_6") (pintype "unspecified"))
    )
    (net (code "29") (name "Net-(USB1-CC1)") (class "Default")
      (node (ref "R1") (pin "2") (pinfunction "2_2") (pintype "input"))
      (node (ref "USB1") (pin "A5") (pinfunction "CC1_A5") (pintype "unspecified"))
    )
    (net (code "30") (name "Net-(USB1-CC2)") (class "Default")
      (node (ref "R2") (pin "1") (pinfunction "1_1") (pintype "input"))
      (node (ref "USB1") (pin "B5") (pinfunction "CC2_B5") (pintype "unspecified"))
    )
    (net (code "31") (name "RESET") (class "Default")
      (node (ref "SW1") (pin "1") (pinfunction "1_1") (pintype "input"))
      (node (ref "U1") (pin "17") (pinfunction "RESET_17") (pintype "unspecified"))
    )
    (net (code "32") (name "USB_D+") (class "Default")
      (node (ref "U1") (pin "3") (pinfunction "USB_D+_3") (pintype "unspecified"))
      (node (ref "USB1") (pin "A6") (pinfunction "DP1_A6") (pintype "unspecified"))
      (node (ref "USB1") (pin "B6") (pinfunction "DP2_B6") (pintype "unspecified"))
    )
    (net (code "33") (name "USB_D-") (class "Default")
      (node (ref "U1") (pin "2") (pinfunction "USB_D-_2") (pintype "unspecified"))
      (node (ref "USB1") (pin "A7") (pinfunction "DN1_A7") (pintype "unspecified"))
      (node (ref "USB1") (pin "B7") (pinfunction "DN2_B7") (pintype "unspecified"))
    )
    (net (code "34") (name "unconnected-(D6-I{slash}O1-Pad1)") (class "Default")
      (node (ref "D6") (pin "1") (pinfunction "I/O1_1") (pintype "unspecified+no_connect"))
    )
    (net (code "35") (name "unconnected-(D6-Vref-Pad5)") (class "Default")
      (node (ref "D6") (pin "5") (pinfunction "Vref_5") (pintype "unspecified+no_connect"))
    )
    (net (code "36") (name "unconnected-(U1-GPIO1-Pad26)") (class "Default")
      (node (ref "U1") (pin "26") (pinfunction "GPIO1_26") (pintype "unspecified+no_connect"))
    )
    (net (code "37") (name "unconnected-(U1-GPIO2-Pad27)") (class "Default")
      (node (ref "U1") (pin "27") (pinfunction "GPIO2_27") (pintype "unspecified+no_connect"))
    )
    (net (code "38") (name "unconnected-(U1-GPIO4{slash}NC-Pad29)") (class "Default")
      (node (ref "U1") (pin "29") (pinfunction "GPIO4/NC_29") (pintype "unspecified+no_connect"))
    )
    (net (code "39") (name "unconnected-(U1-GPIO10{slash}SPI_MISO-Pad30)") (class "Default")
      (node (ref "U1") (pin "30") (pinfunction "GPIO10/SPI_MISO_30") (pintype "unspecified+no_connect"))
    )
    (net (code "40") (name "unconnected-(U1-GPIO11{slash}SPI_MOSI-Pad31)") (class "Default")
      (node (ref "U1") (pin "31") (pinfunction "GPIO11/SPI_MOSI_31") (pintype "unspecified+no_connect"))
    )
    (net (code "41") (name "unconnected-(U1-GPIO12{slash}SPI_CS-Pad32)") (class "Default")
      (node (ref "U1") (pin "32") (pinfunction "GPIO12/SPI_CS_32") (pintype "unspecified+no_connect"))
    )
    (net (code "42") (name "unconnected-(U1-GPIO13{slash}SPI_SCK-Pad33)") (class "Default")
      (node (ref "U1") (pin "33") (pinfunction "GPIO13/SPI_SCK_33") (pintype "unspecified+no_connect"))
    )
    (net (code "43") (name "unconnected-(U1-GPIO14{slash}AIN1-Pad34)") (class "Default")
      (node (ref "U1") (pin "34") (pinfunction "GPIO14/AIN1_34") (pintype "unspecified+no_connect"))
    )
    (net (code "44") (name "unconnected-(U1-GPIO17{slash}I2C2_SDA-Pad40)") (class "Default")
      (node (ref "U1") (pin "40") (pinfunction "GPIO17/I2C2_SDA_40") (pintype "unspecified+no_connect"))
    )
    (net (code "45") (name "unconnected-(U1-GPIO18{slash}I2C2_SCL-Pad39)") (class "Default")
      (node (ref "U1") (pin "39") (pinfunction "GPIO18/I2C2_SCL_39") (pintype "unspecified+no_connect"))
    )
    (net (code "46") (name "unconnected-(U1-GPIO33{slash}NC-Pad4)") (class "Default")
      (node (ref "U1") (pin "4") (pinfunction "GPIO33/NC_4") (pintype "unspecified+no_connect"))
    )
    (net (code "47") (name "unconnected-(U1-GPIO34{slash}NC-Pad5)") (class "Default")
      (node (ref "U1") (pin "5") (pinfunction "GPIO34/NC_5") (pintype "unspecified+no_connect"))
    )
    (net (code "48") (name "unconnected-(U1-GPIO35{slash}NC-Pad8)") (class "Default")
      (node (ref "U1") (pin "8") (pinfunction "GPIO35/NC_8") (pintype "unspecified+no_connect"))
    )
    (net (code "49") (name "unconnected-(U1-GPIO36{slash}NC-Pad9)") (class "Default")
      (node (ref "U1") (pin "9") (pinfunction "GPIO36/NC_9") (pintype "unspecified+no_connect"))
    )
    (net (code "50") (name "unconnected-(U1-GPIO37{slash}NC-Pad10)") (class "Default")
      (node (ref "U1") (pin "10") (pinfunction "GPIO37/NC_10") (pintype "unspecified+no_connect"))
    )
    (net (code "51") (name "unconnected-(U1-GPIO39-Pad12)") (class "Default")
      (node (ref "U1") (pin "12") (pinfunction "GPIO39_12") (pintype "unspecified+no_connect"))
    )
    (net (code "52") (name "unconnected-(U1-GPIO41-Pad18)") (class "Default")
      (node (ref "U1") (pin "18") (pinfunction "GPIO41_18") (pintype "unspecified+no_connect"))
    )
    (net (code "53") (name "unconnected-(U1-GPIO42-Pad19)") (class "Default")
      (node (ref "U1") (pin "19") (pinfunction "GPIO42_19") (pintype "unspecified+no_connect"))
    )
    (net (code "54") (name "unconnected-(U1-GPIO45-Pad23)") (class "Default")
      (node (ref "U1") (pin "23") (pinfunction "GPIO45_23") (pintype "unspecified+no_connect"))
    )
    (net (code "55") (name "unconnected-(U1-GPIO46-Pad25)") (class "Default")
      (node (ref "U1") (pin "25") (pinfunction "GPIO46_25") (pintype "unspecified+no_connect"))
    )
    (net (code "56") (name "unconnected-(U1-NC-Pad1)") (class "Default")
      (node (ref "U1") (pin "1") (pinfunction "NC_1") (pintype "unspecified+no_connect"))
    )
    (net (code "57") (name "unconnected-(U1-NC-Pad43)") (class "Default")
      (node (ref "U1") (pin "43") (pinfunction "NC_43") (pintype "unspecified+no_connect"))
    )
    (net (code "58") (name "unconnected-(U1-NC-Pad44)") (class "Default")
      (node (ref "U1") (pin "44") (pinfunction "NC_44") (pintype "unspecified+no_connect"))
    )
    (net (code "59") (name "unconnected-(U1-RF_LoRa-Pad37)") (class "Default")
      (node (ref "U1") (pin "37") (pinfunction "RF_LoRa_37") (pintype "unspecified+no_connect"))
    )
    (net (code "60") (name "unconnected-(U1-RF_WiFi-Pad15)") (class "Default")
      (node (ref "U1") (pin "15") (pinfunction "RF_WiFi_15") (pintype "unspecified+no_connect"))
    )
    (net (code "61") (name "unconnected-(U10-R2OUT-Pad9)") (class "Default")
      (node (ref "U10") (pin "9") (pinfunction "R2OUT_9") (pintype "unspecified+no_connect"))
    )
    (net (code "62") (name "unconnected-(U10-T2OUT-Pad7)") (class "Default")
      (node (ref "U10") (pin "7") (pinfunction "T2OUT_7") (pintype "unspecified+no_connect"))
    )
    (net (code "63") (name "unconnected-(U11-DOUT-Pad2)") (class "Default")
      (node (ref "U11") (pin "2") (pinfunction "DOUT_2") (pintype "unspecified+no_connect"))
    )
    (net (code "64") (name "unconnected-(USB1-SUB1-PadA8)") (class "Default")
      (node (ref "USB1") (pin "A8") (pinfunction "SUB1_A8") (pintype "unspecified+no_connect"))
    )
    (net (code "65") (name "unconnected-(USB1-SUB2-PadB8)") (class "Default")
      (node (ref "USB1") (pin "B8") (pinfunction "SUB2_B8") (pintype "unspecified+no_connect"))
    )
  )
)
